# Test_Board.net
KiCad netlist of a schematic drawn in EAGLE
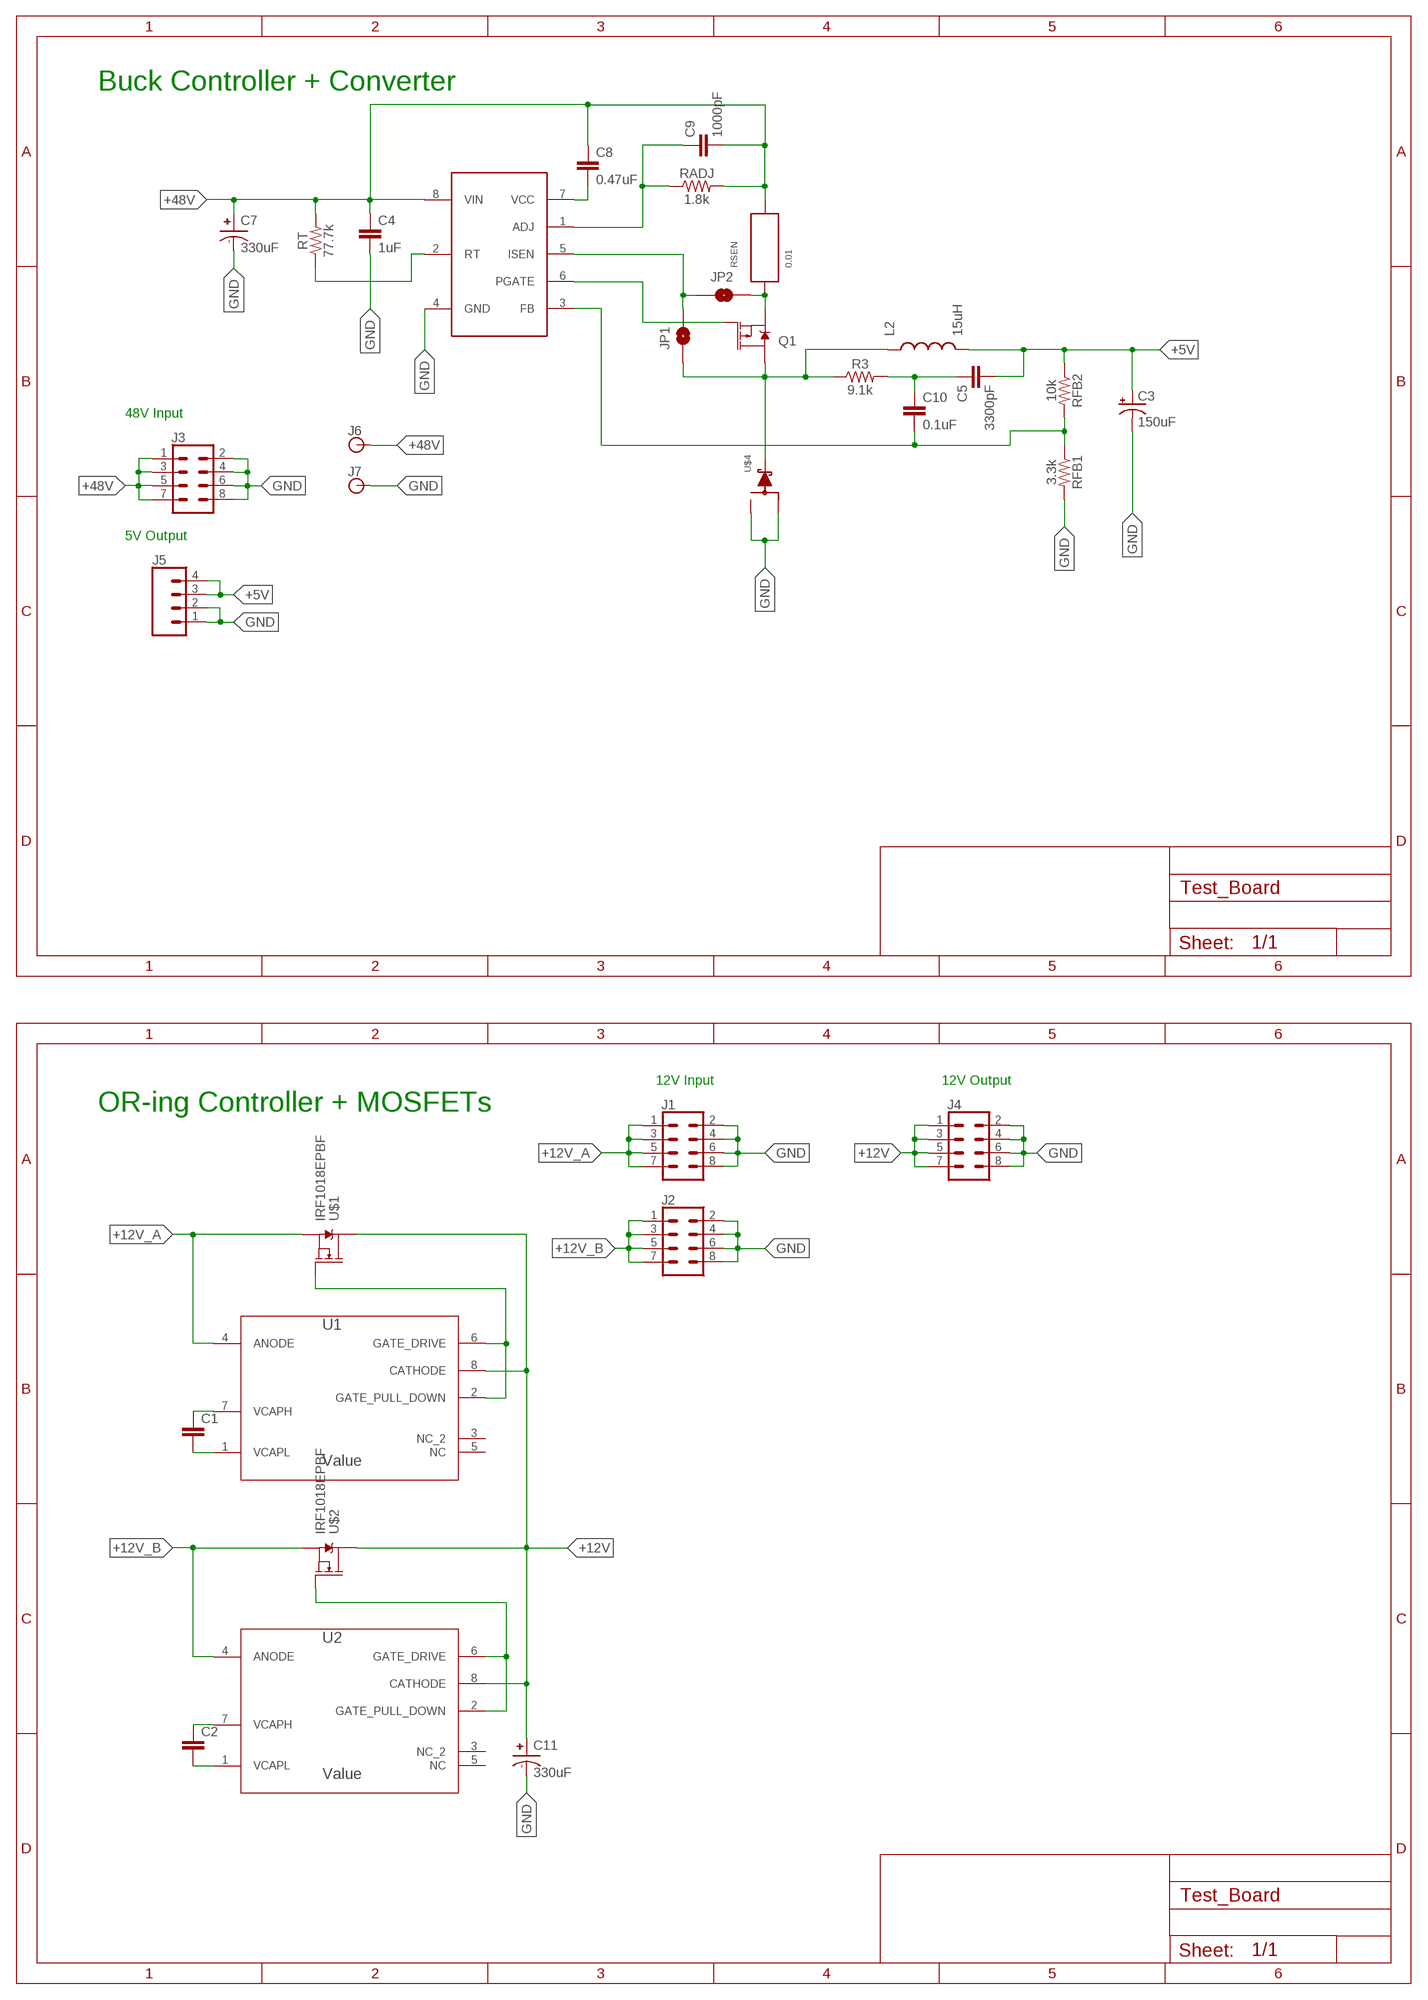
[diagram p0: schematic, sheet 1]

(export (version "E")
  (design (tool "Eeschema 10.0.6"))
  (components
    (comp (ref "C1")
      (value "0.1UF-0603-100V-10%")
      (footprint "eagle-import:0603")
      (libsource (lib "eagle-import") (part "0.1UF-0603-100V-10%"))
    )
    (comp (ref "C2")
      (value "0.1UF-0603-100V-10%")
      (footprint "eagle-import:0603")
      (libsource (lib "eagle-import") (part "0.1UF-0603-100V-10%"))
    )
    (comp (ref "C3")
      (value "150uF")
      (footprint "eagle-import:CTAN(7.30_4.30MM)")
      (libsource (lib "eagle-import") (part "C-TANTALUM(10UF_150UF)"))
    )
    (comp (ref "C4")
      (value "1uF")
      (footprint "eagle-import:0603")
      (libsource (lib "eagle-import") (part "0.1UF-0603-25V-(+80/-20%)"))
    )
    (comp (ref "C5")
      (value "3300pF")
      (footprint "eagle-import:0603")
      (libsource (lib "eagle-import") (part "0.1UF-0603-25V-(+80/-20%)"))
    )
    (comp (ref "C7")
      (value "330uF")
      (footprint "eagle-import:CAPAE1030X1050N")
      (fields
        (field (name "ARROW_PART_NUMBER") "UCM1H331MNL1GS")
        (field (name "MOUSER_PART_NUMBER") "647-UCM1H331MNL1GS")
      )
      (libsource (lib "eagle-import") (part "UCM1H331MNL1GS"))
    )
    (comp (ref "C8")
      (value "0.47uF")
      (footprint "eagle-import:0603")
      (libsource (lib "eagle-import") (part "0.1UF-0603-25V-5%"))
    )
    (comp (ref "C9")
      (value "1000pF")
      (footprint "eagle-import:0603")
      (libsource (lib "eagle-import") (part "0.1UF-0603-25V-5%"))
    )
    (comp (ref "C10")
      (value "0.1uF")
      (footprint "eagle-import:0603")
      (libsource (lib "eagle-import") (part "0.1UF-0603-25V-(+80/-20%)"))
    )
    (comp (ref "C11")
      (value "330uF")
      (footprint "eagle-import:CAPAE1030X1050N")
      (fields
        (field (name "ARROW_PART_NUMBER") "UCM1H331MNL1GS")
        (field (name "MOUSER_PART_NUMBER") "647-UCM1H331MNL1GS")
      )
      (libsource (lib "eagle-import") (part "UCM1H331MNL1GS"))
    )
    (comp (ref "J1")
      (value "CONN_04X2")
      (footprint "eagle-import:2X4")
      (libsource (lib "eagle-import") (part "CONN_04X2"))
    )
    (comp (ref "J2")
      (value "CONN_04X2")
      (footprint "eagle-import:2X4")
      (libsource (lib "eagle-import") (part "CONN_04X2"))
    )
    (comp (ref "J3")
      (value "CONN_04X2")
      (footprint "eagle-import:2X4")
      (libsource (lib "eagle-import") (part "CONN_04X2"))
    )
    (comp (ref "J4")
      (value "CONN_04X2")
      (footprint "eagle-import:2X4")
      (libsource (lib "eagle-import") (part "CONN_04X2"))
    )
    (comp (ref "J5")
      (value "CONN_041X04_NO_SILK")
      (footprint "eagle-import:1X04_NO_SILK")
      (libsource (lib "eagle-import") (part "CONN_041X04_NO_SILK"))
    )
    (comp (ref "J6")
      (value "BANANA_CONN")
      (footprint "eagle-import:BANANA_CONN")
      (libsource (lib "eagle-import") (part "BANANA_CONN"))
    )
    (comp (ref "J7")
      (value "BANANA_CONN")
      (footprint "eagle-import:BANANA_CONN")
      (libsource (lib "eagle-import") (part "BANANA_CONN"))
    )
    (comp (ref "JP1")
      (value "JUMPER-SMT_2_NO_NO-SILK")
      (footprint "eagle-import:SMT-JUMPER_2_NO_NO-SILK")
      (libsource (lib "eagle-import") (part "JUMPER-SMT_2_NO_NO-SILK"))
    )
    (comp (ref "JP2")
      (value "JUMPER-SMT_2_NO_NO-SILK")
      (footprint "eagle-import:SMT-JUMPER_2_NO_NO-SILK")
      (libsource (lib "eagle-import") (part "JUMPER-SMT_2_NO_NO-SILK"))
    )
    (comp (ref "L2")
      (value "15uH")
      (footprint "eagle-import:HCMA1305")
      (libsource (lib "eagle-import") (part "HCMA1305"))
    )
    (comp (ref "Q1")
      (value "MOSFET_PCH-NDS8434")
      (footprint "eagle-import:SO08")
      (libsource (lib "eagle-import") (part "MOSFET_PCH-NDS8434"))
    )
    (comp (ref "R3")
      (value "9.1k")
      (footprint "eagle-import:0603")
      (libsource (lib "eagle-import") (part "RESISTOR0603"))
    )
    (comp (ref "RADJ")
      (value "1.8k")
      (footprint "eagle-import:0603")
      (libsource (lib "eagle-import") (part "RESISTOR0603"))
    )
    (comp (ref "RFB1")
      (value "3.3k")
      (footprint "eagle-import:0603")
      (libsource (lib "eagle-import") (part "RESISTOR0603"))
    )
    (comp (ref "RFB2")
      (value "10k")
      (footprint "eagle-import:0603")
      (libsource (lib "eagle-import") (part "RESISTOR0603"))
    )
    (comp (ref "RSEN")
      (value "0.01")
      (footprint "eagle-import:CSS2H-2512")
      (libsource (lib "eagle-import") (part "CSS2H-2512"))
    )
    (comp (ref "RT")
      (value "77.7k")
      (footprint "eagle-import:0603")
      (libsource (lib "eagle-import") (part "RESISTOR0603"))
    )
    (comp (ref "U$1")
      (value "IRF1018EPBF")
      (footprint "eagle-import:TO263")
      (libsource (lib "eagle-import") (part "IRF1018EPBF"))
    )
    (comp (ref "U$2")
      (value "IRF1018EPBF")
      (footprint "eagle-import:TO263")
      (libsource (lib "eagle-import") (part "IRF1018EPBF"))
    )
    (comp (ref "U$3")
      (value "LM5085")
      (footprint "eagle-import:LM5085")
      (libsource (lib "eagle-import") (part "LM5085"))
    )
    (comp (ref "U$4")
      (value "SWITCHMODE_SCHOTTKY")
      (footprint "eagle-import:DPAK-3")
      (libsource (lib "eagle-import") (part "SWITCHMODE_SCHOTTKY"))
    )
    (comp (ref "U1")
      (value "Value")
      (footprint "eagle-import:DGK0008A_M")
      (fields (field (name "MANUFACTURER") "Texas Instruments") (field (name "PARTNUMBER") "LM74610QDGKRQ1"))
      (libsource (lib "eagle-import") (part "DIST_OR_DIODEDGK0008A_M"))
    )
    (comp (ref "U2")
      (value "Value")
      (footprint "eagle-import:DGK0008A_M")
      (fields (field (name "MANUFACTURER") "Texas Instruments") (field (name "PARTNUMBER") "LM74610QDGKRQ1"))
      (libsource (lib "eagle-import") (part "DIST_OR_DIODEDGK0008A_M"))
    )
  )
  (nets
    (net (code "1") (name "+5V") (class "Default")
      (node (ref "C3") (pin "+") (pinfunction "+_+") (pintype "passive"))
      (node (ref "C5") (pin "2") (pinfunction "2_2") (pintype "passive"))
      (node (ref "J5") (pin "3") (pinfunction "3_3") (pintype "passive"))
      (node (ref "J5") (pin "4") (pinfunction "4_4") (pintype "passive"))
      (node (ref "L2") (pin "2") (pinfunction "2_2") (pintype "passive"))
      (node (ref "RFB2") (pin "1") (pinfunction "1_1") (pintype "passive"))
    )
    (net (code "2") (name "+12V") (class "Default")
      (node (ref "C11") (pin "+") (pinfunction "+_+") (pintype "bidirectional"))
      (node (ref "J4") (pin "1") (pinfunction "1_1") (pintype "passive"))
      (node (ref "J4") (pin "3") (pinfunction "3_3") (pintype "passive"))
      (node (ref "J4") (pin "5") (pinfunction "5_5") (pintype "passive"))
      (node (ref "J4") (pin "7") (pinfunction "7_7") (pintype "passive"))
      (node (ref "U$1") (pin "3") (pinfunction "D_3") (pintype "bidirectional"))
      (node (ref "U$2") (pin "3") (pinfunction "D_3") (pintype "bidirectional"))
      (node (ref "U1") (pin "8") (pinfunction "CATHODE_8") (pintype "output"))
      (node (ref "U2") (pin "8") (pinfunction "CATHODE_8") (pintype "output"))
    )
    (net (code "3") (name "+12V_A") (class "Default")
      (node (ref "J1") (pin "1") (pinfunction "1_1") (pintype "passive"))
      (node (ref "J1") (pin "3") (pinfunction "3_3") (pintype "passive"))
      (node (ref "J1") (pin "5") (pinfunction "5_5") (pintype "passive"))
      (node (ref "J1") (pin "7") (pinfunction "7_7") (pintype "passive"))
      (node (ref "U$1") (pin "2") (pinfunction "S_2") (pintype "bidirectional"))
      (node (ref "U1") (pin "4") (pinfunction "ANODE_4") (pintype "power_in"))
    )
    (net (code "4") (name "+12V_B") (class "Default")
      (node (ref "J2") (pin "1") (pinfunction "1_1") (pintype "passive"))
      (node (ref "J2") (pin "3") (pinfunction "3_3") (pintype "passive"))
      (node (ref "J2") (pin "5") (pinfunction "5_5") (pintype "passive"))
      (node (ref "J2") (pin "7") (pinfunction "7_7") (pintype "passive"))
      (node (ref "U$2") (pin "2") (pinfunction "S_2") (pintype "bidirectional"))
      (node (ref "U2") (pin "4") (pinfunction "ANODE_4") (pintype "power_in"))
    )
    (net (code "5") (name "+48V") (class "Default")
      (node (ref "C4") (pin "1") (pinfunction "1_1") (pintype "passive"))
      (node (ref "C7") (pin "+") (pinfunction "+_+") (pintype "bidirectional"))
      (node (ref "C8") (pin "1") (pinfunction "1_1") (pintype "passive"))
      (node (ref "C9") (pin "2") (pinfunction "2_2") (pintype "passive"))
      (node (ref "J3") (pin "1") (pinfunction "1_1") (pintype "passive"))
      (node (ref "J3") (pin "3") (pinfunction "3_3") (pintype "passive"))
      (node (ref "J3") (pin "5") (pinfunction "5_5") (pintype "passive"))
      (node (ref "J3") (pin "7") (pinfunction "7_7") (pintype "passive"))
      (node (ref "J6") (pin "P$1") (pinfunction "1_P$1") (pintype "passive"))
      (node (ref "RADJ") (pin "2") (pinfunction "2_2") (pintype "passive"))
      (node (ref "RSEN") (pin "2") (pinfunction "2_2") (pintype "bidirectional"))
      (node (ref "RT") (pin "2") (pinfunction "2_2") (pintype "passive"))
      (node (ref "U$3") (pin "8") (pinfunction "VIN_8") (pintype "bidirectional"))
    )
    (net (code "6") (name "GND") (class "Default")
      (node (ref "C11") (pin "-") (pinfunction "-_-") (pintype "bidirectional"))
      (node (ref "C3") (pin "-") (pinfunction "-_-") (pintype "passive"))
      (node (ref "C4") (pin "2") (pinfunction "2_2") (pintype "passive"))
      (node (ref "C7") (pin "-") (pinfunction "-_-") (pintype "bidirectional"))
      (node (ref "J1") (pin "2") (pinfunction "2_2") (pintype "passive"))
      (node (ref "J1") (pin "4") (pinfunction "4_4") (pintype "passive"))
      (node (ref "J1") (pin "6") (pinfunction "6_6") (pintype "passive"))
      (node (ref "J1") (pin "8") (pinfunction "8_8") (pintype "passive"))
      (node (ref "J2") (pin "2") (pinfunction "2_2") (pintype "passive"))
      (node (ref "J2") (pin "4") (pinfunction "4_4") (pintype "passive"))
      (node (ref "J2") (pin "6") (pinfunction "6_6") (pintype "passive"))
      (node (ref "J2") (pin "8") (pinfunction "8_8") (pintype "passive"))
      (node (ref "J3") (pin "2") (pinfunction "2_2") (pintype "passive"))
      (node (ref "J3") (pin "4") (pinfunction "4_4") (pintype "passive"))
      (node (ref "J3") (pin "6") (pinfunction "6_6") (pintype "passive"))
      (node (ref "J3") (pin "8") (pinfunction "8_8") (pintype "passive"))
      (node (ref "J4") (pin "2") (pinfunction "2_2") (pintype "passive"))
      (node (ref "J4") (pin "4") (pinfunction "4_4") (pintype "passive"))
      (node (ref "J4") (pin "6") (pinfunction "6_6") (pintype "passive"))
      (node (ref "J4") (pin "8") (pinfunction "8_8") (pintype "passive"))
      (node (ref "J5") (pin "1") (pinfunction "1_1") (pintype "passive"))
      (node (ref "J5") (pin "2") (pinfunction "2_2") (pintype "passive"))
      (node (ref "J7") (pin "P$1") (pinfunction "1_P$1") (pintype "passive"))
      (node (ref "RFB1") (pin "2") (pinfunction "2_2") (pintype "passive"))
      (node (ref "U$3") (pin "4") (pinfunction "GND_4") (pintype "bidirectional"))
      (node (ref "U$4") (pin "P$1") (pinfunction "P$1_P$1") (pintype "bidirectional"))
      (node (ref "U$4") (pin "P$3") (pinfunction "P$3_P$3") (pintype "bidirectional"))
    )
    (net (code "7") (name "Net-(C10-Pad1)") (class "Default")
      (node (ref "C10") (pin "1") (pinfunction "1_1") (pintype "passive"))
      (node (ref "C5") (pin "1") (pinfunction "1_1") (pintype "passive"))
      (node (ref "R3") (pin "2") (pinfunction "2_2") (pintype "passive"))
    )
    (net (code "8") (name "Net-(JP1-Pad1)") (class "Default")
      (node (ref "JP1") (pin "1") (pinfunction "1_1") (pintype "passive"))
      (node (ref "L2") (pin "1") (pinfunction "1_1") (pintype "passive"))
      (node (ref "Q1") (pin "5") (pinfunction "D_5") (pintype "bidirectional"))
      (node (ref "Q1") (pin "6") (pinfunction "D_6") (pintype "bidirectional"))
      (node (ref "Q1") (pin "7") (pinfunction "D_7") (pintype "bidirectional"))
      (node (ref "Q1") (pin "8") (pinfunction "D_8") (pintype "bidirectional"))
      (node (ref "R3") (pin "1") (pinfunction "1_1") (pintype "passive"))
      (node (ref "U$4") (pin "P$4") (pinfunction "P$4_P$4") (pintype "bidirectional"))
    )
    (net (code "9") (name "Net-(JP2-Pad2)") (class "Default")
      (node (ref "JP2") (pin "2") (pinfunction "2_2") (pintype "passive"))
      (node (ref "Q1") (pin "1") (pinfunction "S_1") (pintype "bidirectional"))
      (node (ref "Q1") (pin "2") (pinfunction "S_2") (pintype "bidirectional"))
      (node (ref "Q1") (pin "3") (pinfunction "S_3") (pintype "bidirectional"))
      (node (ref "RSEN") (pin "1") (pinfunction "1_1") (pintype "bidirectional"))
    )
    (net (code "10") (name "Net-(Q1-G)") (class "Default")
      (node (ref "Q1") (pin "4") (pinfunction "G_4") (pintype "bidirectional"))
      (node (ref "U$3") (pin "6") (pinfunction "PGATE_6") (pintype "bidirectional"))
    )
    (net (code "11") (name "Net-(U$1-G)") (class "Default")
      (node (ref "U$1") (pin "1") (pinfunction "G_1") (pintype "bidirectional"))
      (node (ref "U1") (pin "2") (pinfunction "GATE_PULL_DOWN_2") (pintype "passive"))
      (node (ref "U1") (pin "6") (pinfunction "GATE_DRIVE_6") (pintype "output"))
    )
    (net (code "12") (name "Net-(U$2-G)") (class "Default")
      (node (ref "U$2") (pin "1") (pinfunction "G_1") (pintype "bidirectional"))
      (node (ref "U2") (pin "2") (pinfunction "GATE_PULL_DOWN_2") (pintype "passive"))
      (node (ref "U2") (pin "6") (pinfunction "GATE_DRIVE_6") (pintype "output"))
    )
    (net (code "13") (name "Net-(U$3-ADJ)") (class "Default")
      (node (ref "C9") (pin "1") (pinfunction "1_1") (pintype "passive"))
      (node (ref "RADJ") (pin "1") (pinfunction "1_1") (pintype "passive"))
      (node (ref "U$3") (pin "1") (pinfunction "ADJ_1") (pintype "bidirectional"))
    )
    (net (code "14") (name "Net-(U$3-FB)") (class "Default")
      (node (ref "C10") (pin "2") (pinfunction "2_2") (pintype "passive"))
      (node (ref "RFB1") (pin "1") (pinfunction "1_1") (pintype "passive"))
      (node (ref "RFB2") (pin "2") (pinfunction "2_2") (pintype "passive"))
      (node (ref "U$3") (pin "3") (pinfunction "FB_3") (pintype "bidirectional"))
    )
    (net (code "15") (name "Net-(U$3-ISEN)") (class "Default")
      (node (ref "JP1") (pin "2") (pinfunction "2_2") (pintype "passive"))
      (node (ref "JP2") (pin "1") (pinfunction "1_1") (pintype "passive"))
      (node (ref "U$3") (pin "5") (pinfunction "ISEN_5") (pintype "bidirectional"))
    )
    (net (code "16") (name "Net-(U$3-RT)") (class "Default")
      (node (ref "RT") (pin "1") (pinfunction "1_1") (pintype "passive"))
      (node (ref "U$3") (pin "2") (pinfunction "RT_2") (pintype "bidirectional"))
    )
    (net (code "17") (name "Net-(U$3-VCC)") (class "Default")
      (node (ref "C8") (pin "2") (pinfunction "2_2") (pintype "passive"))
      (node (ref "U$3") (pin "7") (pinfunction "VCC_7") (pintype "bidirectional"))
    )
    (net (code "18") (name "Net-(U1-VCAPH)") (class "Default")
      (node (ref "C1") (pin "1") (pinfunction "1_1") (pintype "passive"))
      (node (ref "U1") (pin "7") (pinfunction "VCAPH_7") (pintype "passive"))
    )
    (net (code "19") (name "Net-(U1-VCAPL)") (class "Default")
      (node (ref "C1") (pin "2") (pinfunction "2_2") (pintype "passive"))
      (node (ref "U1") (pin "1") (pinfunction "VCAPL_1") (pintype "passive"))
    )
    (net (code "20") (name "Net-(U2-VCAPH)") (class "Default")
      (node (ref "C2") (pin "1") (pinfunction "1_1") (pintype "passive"))
      (node (ref "U2") (pin "7") (pinfunction "VCAPH_7") (pintype "passive"))
    )
    (net (code "21") (name "Net-(U2-VCAPL)") (class "Default")
      (node (ref "C2") (pin "2") (pinfunction "2_2") (pintype "passive"))
      (node (ref "U2") (pin "1") (pinfunction "VCAPL_1") (pintype "passive"))
    )
    (net (code "22") (name "unconnected-(U1-NC-Pad5)") (class "Default")
      (node (ref "U1") (pin "5") (pinfunction "NC_5") (pintype "passive"))
    )
    (net (code "23") (name "unconnected-(U1-NC_2-Pad3)") (class "Default")
      (node (ref "U1") (pin "3") (pinfunction "NC_2_3") (pintype "passive"))
    )
    (net (code "24") (name "unconnected-(U2-NC-Pad5)") (class "Default")
      (node (ref "U2") (pin "5") (pinfunction "NC_5") (pintype "passive"))
    )
    (net (code "25") (name "unconnected-(U2-NC_2-Pad3)") (class "Default")
      (node (ref "U2") (pin "3") (pinfunction "NC_2_3") (pintype "passive"))
    )
  )
)
